# STM32_USB.net
KiCad netlist of a schematic drawn in Altium Designer
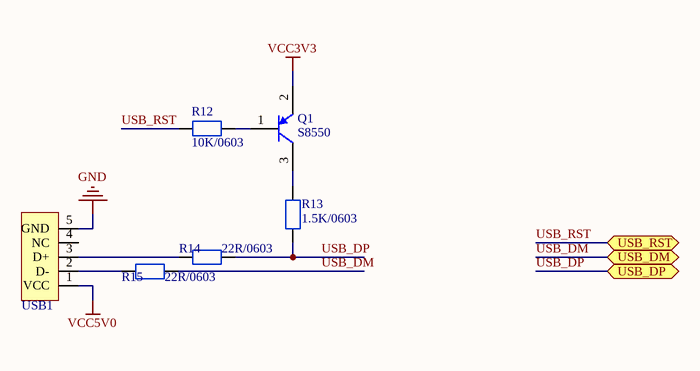
[diagram p0: STM32_USB.SchDoc]

(export (version "E")
  (design (tool "Eeschema 10.0.6"))
  (components
    (comp (ref "Q1") (value "S8550") (footprint "SOT-23") (libsource (lib "常用原件") (part "S8550")))
    (comp (ref "R12") (value "10K/0603") (footprint "R0603") (libsource (lib "常用原件") (part "RES")))
    (comp (ref "R13") (value "1.5K/0603") (footprint "R0603") (libsource (lib "常用原件") (part "RES")))
    (comp (ref "R14") (value "22R/0603") (footprint "R0603") (libsource (lib "常用原件") (part "RES")))
    (comp (ref "R15") (value "22R/0603") (footprint "R0603") (libsource (lib "常用原件") (part "RES")))
    (comp (ref "USB1") (value "USB-Mini") (footprint "USB-Mini") (libsource (lib "常用原件") (part "USB-Mini")))
  )
  (nets
    (net (code "1") (name "/USB_DM") (class "Default")
      (node (ref "R15") (pin "2") (pinfunction "2_2") (pintype "passive"))
    )
    (net (code "2") (name "/USB_DP") (class "Default")
      (node (ref "R13") (pin "1") (pinfunction "1_1") (pintype "passive"))
      (node (ref "R14") (pin "2") (pinfunction "2_2") (pintype "passive"))
    )
    (net (code "3") (name "/USB_RST") (class "Default")
      (node (ref "R12") (pin "2") (pinfunction "2_2") (pintype "passive"))
    )
    (net (code "4") (name "GND") (class "Default")
      (node (ref "USB1") (pin "5") (pinfunction "GND_5") (pintype "passive"))
    )
    (net (code "5") (name "Net-(Q1-B)") (class "Default")
      (node (ref "Q1") (pin "1") (pinfunction "B_1") (pintype "passive"))
      (node (ref "R12") (pin "1") (pinfunction "1_1") (pintype "passive"))
    )
    (net (code "6") (name "Net-(Q1-C)") (class "Default")
      (node (ref "Q1") (pin "3") (pinfunction "C_3") (pintype "passive"))
      (node (ref "R13") (pin "2") (pinfunction "2_2") (pintype "passive"))
    )
    (net (code "7") (name "Net-(USB1-D+)") (class "Default")
      (node (ref "R14") (pin "1") (pinfunction "1_1") (pintype "passive"))
      (node (ref "USB1") (pin "3") (pinfunction "D+_3") (pintype "passive"))
    )
    (net (code "8") (name "Net-(USB1-D-)") (class "Default")
      (node (ref "R15") (pin "1") (pinfunction "1_1") (pintype "passive"))
      (node (ref "USB1") (pin "2") (pinfunction "D-_2") (pintype "passive"))
    )
    (net (code "9") (name "VCC3V3") (class "Default")
      (node (ref "Q1") (pin "2") (pinfunction "E_2") (pintype "passive"))
    )
    (net (code "10") (name "VCC5V0") (class "Default")
      (node (ref "USB1") (pin "1") (pinfunction "VCC_1") (pintype "passive"))
    )
    (net (code "11") (name "unconnected-(USB1-NC-Pad4)") (class "Default")
      (node (ref "USB1") (pin "4") (pinfunction "NC_4") (pintype "passive"))
    )
  )
)
